# tomada.net
KiCad netlist of a schematic drawn in EAGLE
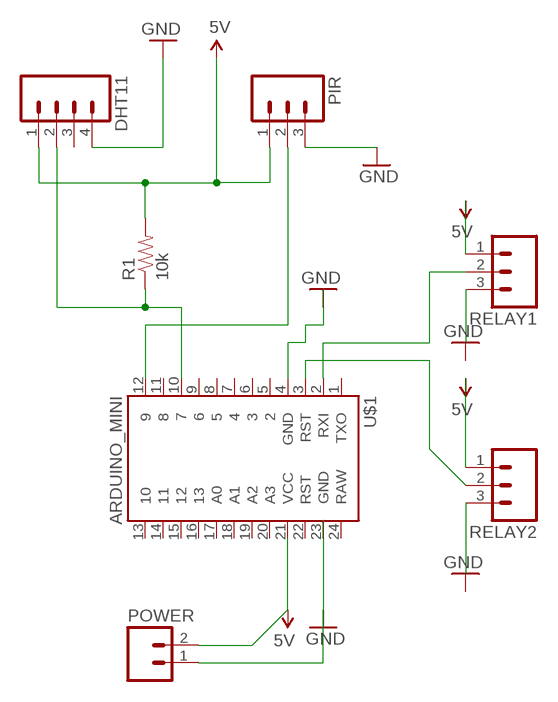
[diagram p0: schematic, sheet 1]

(export (version "E")
  (design (tool "Eeschema 10.0.6"))
  (components
    (comp (ref "DHT11")
      (value "M04PTH")
      (footprint "eagle-import:1X04")
      (libsource (lib "eagle-import") (part "M04PTH"))
    )
    (comp (ref "PIR")
      (value "M03PTH")
      (footprint "eagle-import:1X03")
      (libsource (lib "eagle-import") (part "M03PTH"))
    )
    (comp (ref "POWER")
      (value "M02PTH4")
      (footprint "eagle-import:1X02_XTRA_BIG")
      (libsource (lib "eagle-import") (part "M02PTH4"))
    )
    (comp (ref "R1")
      (value "10k")
      (footprint "eagle-import:AXIAL-0.4")
      (libsource (lib "eagle-import") (part "RESISTORPTH-1/4W"))
    )
    (comp (ref "RELAY1")
      (value "M03PTH")
      (footprint "eagle-import:1X03")
      (libsource (lib "eagle-import") (part "M03PTH"))
    )
    (comp (ref "RELAY2")
      (value "M03PTH")
      (footprint "eagle-import:1X03")
      (libsource (lib "eagle-import") (part "M03PTH"))
    )
    (comp (ref "U$1")
      (value "ARDUINO_MINI")
      (footprint "eagle-import:ARDUINO_MINI")
      (libsource (lib "eagle-import") (part "ARDUINO_MINI"))
    )
  )
  (nets
    (net (code "1") (name "5V") (class "Default")
      (node (ref "DHT11") (pin "1") (pinfunction "1_1") (pintype "passive"))
      (node (ref "PIR") (pin "1") (pinfunction "1_1") (pintype "passive"))
      (node (ref "POWER") (pin "2") (pinfunction "2_2") (pintype "passive"))
      (node (ref "R1") (pin "P$2") (pinfunction "2_P$2") (pintype "passive"))
      (node (ref "RELAY1") (pin "1") (pinfunction "1_1") (pintype "passive"))
      (node (ref "RELAY2") (pin "1") (pinfunction "1_1") (pintype "passive"))
      (node (ref "U$1") (pin "21") (pinfunction "VCC_21") (pintype "bidirectional"))
    )
    (net (code "2") (name "GND") (class "Default")
      (node (ref "DHT11") (pin "4") (pinfunction "4_4") (pintype "passive"))
      (node (ref "PIR") (pin "3") (pinfunction "3_3") (pintype "passive"))
      (node (ref "POWER") (pin "1") (pinfunction "1_1") (pintype "passive"))
    )
    (net (code "3") (name "Net-(R1-1)") (class "Default")
      (node (ref "DHT11") (pin "2") (pinfunction "2_2") (pintype "passive"))
      (node (ref "R1") (pin "P$1") (pinfunction "1_P$1") (pintype "passive"))
      (node (ref "U$1") (pin "10") (pinfunction "7_10") (pintype "bidirectional"))
    )
    (net (code "4") (name "Net-(RELAY2-Pad2)") (class "Default")
      (node (ref "RELAY2") (pin "2") (pinfunction "2_2") (pintype "passive"))
      (node (ref "U$1") (pin "3") (pinfunction "RST_3") (pintype "bidirectional"))
    )
    (net (code "5") (name "Net-(U$1-9)") (class "Default")
      (node (ref "PIR") (pin "2") (pinfunction "2_2") (pintype "passive"))
      (node (ref "U$1") (pin "12") (pinfunction "9_12") (pintype "bidirectional"))
    )
    (net (code "6") (name "Net-(U$1-RXI)") (class "Default")
      (node (ref "RELAY1") (pin "2") (pinfunction "2_2") (pintype "passive"))
      (node (ref "U$1") (pin "2") (pinfunction "RXI_2") (pintype "bidirectional"))
    )
    (net (code "7") (name "unconnected-(DHT11-Pad3)") (class "Default")
      (node (ref "DHT11") (pin "3") (pinfunction "3_3") (pintype "passive"))
    )
    (net (code "8") (name "unconnected-(RELAY1-Pad3)") (class "Default")
      (node (ref "RELAY1") (pin "3") (pinfunction "3_3") (pintype "passive"))
    )
    (net (code "9") (name "unconnected-(RELAY2-Pad3)") (class "Default")
      (node (ref "RELAY2") (pin "3") (pinfunction "3_3") (pintype "passive"))
    )
    (net (code "10") (name "unconnected-(U$1-2-Pad5)") (class "Default")
      (node (ref "U$1") (pin "5") (pinfunction "2_5") (pintype "bidirectional"))
    )
    (net (code "11") (name "unconnected-(U$1-3-Pad6)") (class "Default")
      (node (ref "U$1") (pin "6") (pinfunction "3_6") (pintype "bidirectional"))
    )
    (net (code "12") (name "unconnected-(U$1-4-Pad7)") (class "Default")
      (node (ref "U$1") (pin "7") (pinfunction "4_7") (pintype "bidirectional"))
    )
    (net (code "13") (name "unconnected-(U$1-5-Pad8)") (class "Default")
      (node (ref "U$1") (pin "8") (pinfunction "5_8") (pintype "bidirectional"))
    )
    (net (code "14") (name "unconnected-(U$1-6-Pad9)") (class "Default")
      (node (ref "U$1") (pin "9") (pinfunction "6_9") (pintype "bidirectional"))
    )
    (net (code "15") (name "unconnected-(U$1-8-Pad11)") (class "Default")
      (node (ref "U$1") (pin "11") (pinfunction "8_11") (pintype "bidirectional"))
    )
    (net (code "16") (name "unconnected-(U$1-10-Pad13)") (class "Default")
      (node (ref "U$1") (pin "13") (pinfunction "10_13") (pintype "bidirectional"))
    )
    (net (code "17") (name "unconnected-(U$1-11-Pad14)") (class "Default")
      (node (ref "U$1") (pin "14") (pinfunction "11_14") (pintype "bidirectional"))
    )
    (net (code "18") (name "unconnected-(U$1-12-Pad15)") (class "Default")
      (node (ref "U$1") (pin "15") (pinfunction "12_15") (pintype "bidirectional"))
    )
    (net (code "19") (name "unconnected-(U$1-13-Pad16)") (class "Default")
      (node (ref "U$1") (pin "16") (pinfunction "13_16") (pintype "bidirectional"))
    )
    (net (code "20") (name "unconnected-(U$1-A0-Pad17)") (class "Default")
      (node (ref "U$1") (pin "17") (pinfunction "A0_17") (pintype "bidirectional"))
    )
    (net (code "21") (name "unconnected-(U$1-A1-Pad18)") (class "Default")
      (node (ref "U$1") (pin "18") (pinfunction "A1_18") (pintype "bidirectional"))
    )
    (net (code "22") (name "unconnected-(U$1-A2-Pad19)") (class "Default")
      (node (ref "U$1") (pin "19") (pinfunction "A2_19") (pintype "bidirectional"))
    )
    (net (code "23") (name "unconnected-(U$1-A3-Pad20)") (class "Default")
      (node (ref "U$1") (pin "20") (pinfunction "A3_20") (pintype "bidirectional"))
    )
    (net (code "24") (name "unconnected-(U$1-GND-Pad4)") (class "Default")
      (node (ref "U$1") (pin "4") (pinfunction "GND_4") (pintype "bidirectional"))
    )
    (net (code "25") (name "unconnected-(U$1-GND-Pad23)") (class "Default")
      (node (ref "U$1") (pin "23") (pinfunction "GND_23") (pintype "bidirectional"))
    )
    (net (code "26") (name "unconnected-(U$1-RAW-Pad24)") (class "Default")
      (node (ref "U$1") (pin "24") (pinfunction "RAW_24") (pintype "bidirectional"))
    )
    (net (code "27") (name "unconnected-(U$1-RST-Pad22)") (class "Default")
      (node (ref "U$1") (pin "22") (pinfunction "RST_22") (pintype "bidirectional"))
    )
    (net (code "28") (name "unconnected-(U$1-TXO-Pad1)") (class "Default")
      (node (ref "U$1") (pin "1") (pinfunction "TXO_1") (pintype "bidirectional"))
    )
  )
)
